# GS_IIM_RFINAL_R_4.net
KiCad netlist of a schematic drawn in EAGLE
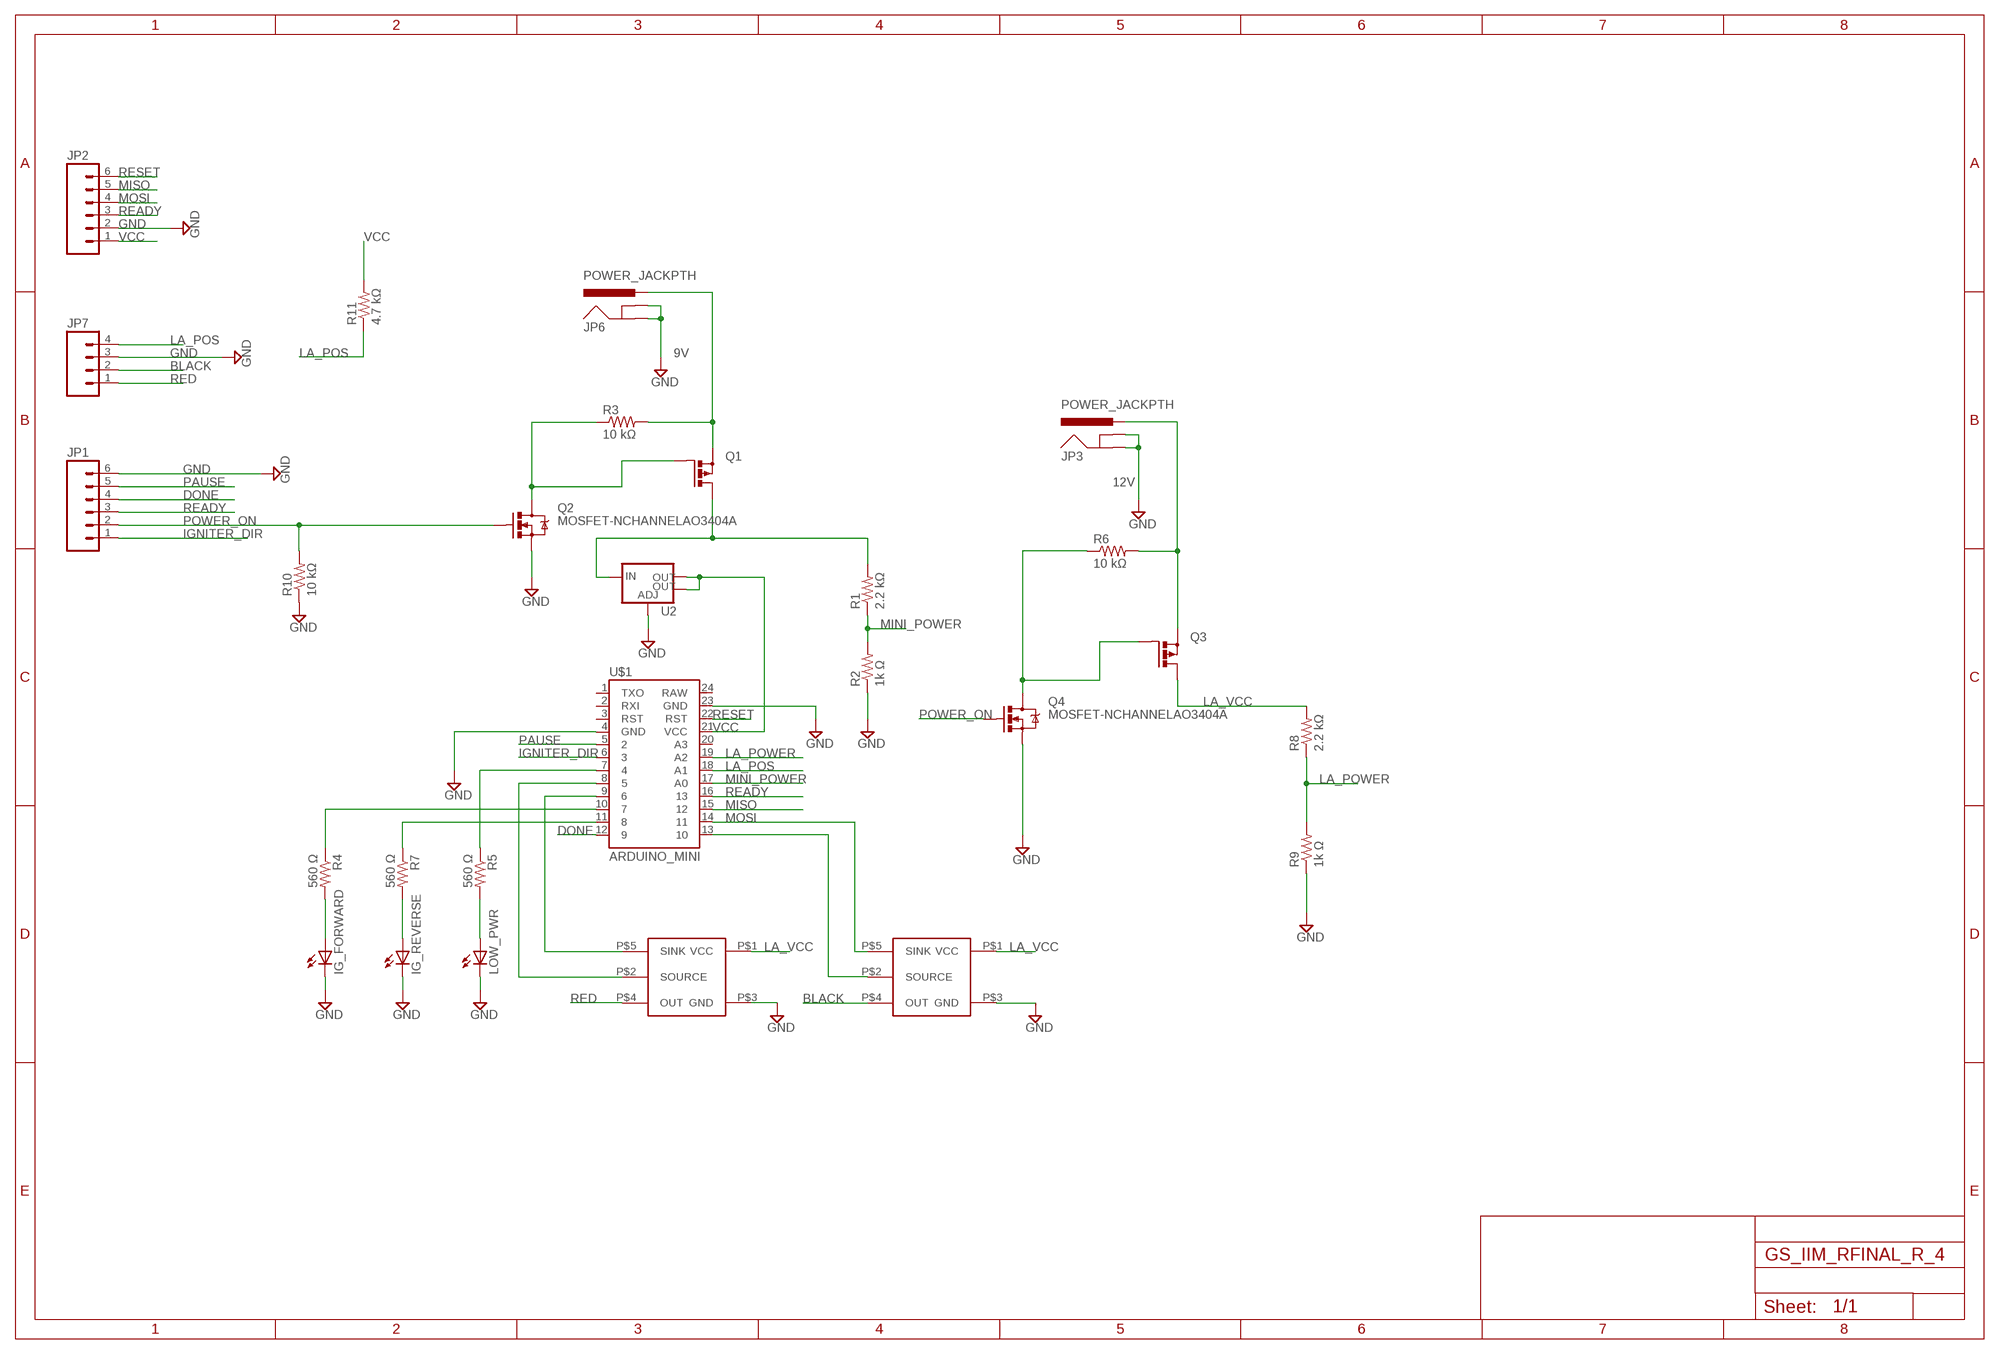
[diagram p0: schematic, sheet 1]

(export (version "E")
  (design (tool "Eeschema 10.0.6"))
  (components
    (comp (ref "IG_FORWARD")
      (value "LED5MM")
      (footprint "eagle-import:LED5MM")
      (libsource (lib "eagle-import") (part "LED5MM"))
    )
    (comp (ref "IG_REVERSE")
      (value "LED5MM")
      (footprint "eagle-import:LED5MM")
      (libsource (lib "eagle-import") (part "LED5MM"))
    )
    (comp (ref "JP1")
      (value "M06SILK_FEMALE_PTH")
      (footprint "eagle-import:1X06")
      (libsource (lib "eagle-import") (part "M06SILK_FEMALE_PTH"))
    )
    (comp (ref "JP2")
      (value "M06SILK_FEMALE_PTH")
      (footprint "eagle-import:1X06")
      (libsource (lib "eagle-import") (part "M06SILK_FEMALE_PTH"))
    )
    (comp (ref "JP3")
      (value "POWER_JACKPTH")
      (footprint "eagle-import:POWER_JACK_PTH")
      (libsource (lib "eagle-import") (part "POWER_JACKPTH"))
    )
    (comp (ref "JP6")
      (value "POWER_JACKPTH")
      (footprint "eagle-import:POWER_JACK_PTH")
      (libsource (lib "eagle-import") (part "POWER_JACKPTH"))
    )
    (comp (ref "JP7")
      (value "M04PTH")
      (footprint "eagle-import:1X04")
      (libsource (lib "eagle-import") (part "M04PTH"))
    )
    (comp (ref "LOW_PWR")
      (value "LED5MM")
      (footprint "eagle-import:LED5MM")
      (libsource (lib "eagle-import") (part "LED5MM"))
    )
    (comp (ref "Q1")
      (value "P-MOSFET-SO8")
      (footprint "eagle-import:SO-08")
      (libsource (lib "eagle-import") (part "P-MOSFET-SO8"))
    )
    (comp (ref "Q2")
      (value "MOSFET-NCHANNELAO3404A")
      (footprint "eagle-import:SOT23-3")
      (libsource (lib "eagle-import") (part "MOSFET-NCHANNELAO3404A"))
    )
    (comp (ref "Q3")
      (value "P-MOSFET-SO8")
      (footprint "eagle-import:SO-08")
      (libsource (lib "eagle-import") (part "P-MOSFET-SO8"))
    )
    (comp (ref "Q4")
      (value "MOSFET-NCHANNELAO3404A")
      (footprint "eagle-import:SOT23-3")
      (libsource (lib "eagle-import") (part "MOSFET-NCHANNELAO3404A"))
    )
    (comp (ref "R1")
      (value "2.2 kΩ")
      (footprint "eagle-import:1206")
      (libsource (lib "eagle-import") (part "RESISTOR1206"))
    )
    (comp (ref "R2")
      (value "1k Ω")
      (footprint "eagle-import:1206")
      (libsource (lib "eagle-import") (part "RESISTOR1206"))
    )
    (comp (ref "R3")
      (value "10 kΩ")
      (footprint "eagle-import:1206")
      (libsource (lib "eagle-import") (part "RESISTOR1206"))
    )
    (comp (ref "R4")
      (value "560 Ω")
      (footprint "eagle-import:1206")
      (libsource (lib "eagle-import") (part "RESISTOR1206"))
    )
    (comp (ref "R5")
      (value "560 Ω")
      (footprint "eagle-import:1206")
      (libsource (lib "eagle-import") (part "RESISTOR1206"))
    )
    (comp (ref "R6")
      (value "10 kΩ")
      (footprint "eagle-import:1206")
      (libsource (lib "eagle-import") (part "RESISTOR1206"))
    )
    (comp (ref "R7")
      (value "560 Ω")
      (footprint "eagle-import:1206")
      (libsource (lib "eagle-import") (part "RESISTOR1206"))
    )
    (comp (ref "R8")
      (value "2.2 kΩ")
      (footprint "eagle-import:1206")
      (libsource (lib "eagle-import") (part "RESISTOR1206"))
    )
    (comp (ref "R9")
      (value "1k Ω")
      (footprint "eagle-import:1206")
      (libsource (lib "eagle-import") (part "RESISTOR1206"))
    )
    (comp (ref "R10")
      (value "10 kΩ")
      (footprint "eagle-import:1206")
      (libsource (lib "eagle-import") (part "RESISTOR1206"))
    )
    (comp (ref "R11")
      (value "4.7 kΩ")
      (footprint "eagle-import:1206")
      (libsource (lib "eagle-import") (part "RESISTOR1206"))
    )
    (comp (ref "U$1")
      (value "ARDUINO_MINI")
      (footprint "eagle-import:ARDUINO_MINI")
      (libsource (lib "eagle-import") (part "ARDUINO_MINI"))
    )
    (comp (ref "U$3")
      (value "UC2950")
      (footprint "eagle-import:TO-220")
      (libsource (lib "eagle-import") (part "UC2950"))
    )
    (comp (ref "U2")
      (value "V_REG_LM1117SOT223")
      (footprint "eagle-import:SOT223")
      (libsource (lib "eagle-import") (part "V_REG_LM1117SOT223"))
    )
    (comp (ref "UC2950_1")
      (value "UC2950")
      (footprint "eagle-import:TO-220")
      (libsource (lib "eagle-import") (part "UC2950"))
    )
  )
  (nets
    (net (code "1") (name "/9V") (class "Default")
      (node (ref "JP6") (pin "PWR") (pinfunction "PWR_PWR") (pintype "bidirectional"))
      (node (ref "Q1") (pin "1") (pinfunction "S_1") (pintype "passive"))
      (node (ref "Q1") (pin "2") (pinfunction "S_2") (pintype "passive"))
      (node (ref "Q1") (pin "3") (pinfunction "S_3") (pintype "passive"))
      (node (ref "R3") (pin "2") (pinfunction "2_2") (pintype "passive"))
    )
    (net (code "2") (name "/12V") (class "Default")
      (node (ref "JP3") (pin "PWR") (pinfunction "PWR_PWR") (pintype "bidirectional"))
      (node (ref "Q3") (pin "1") (pinfunction "S_1") (pintype "passive"))
      (node (ref "Q3") (pin "2") (pinfunction "S_2") (pintype "passive"))
      (node (ref "Q3") (pin "3") (pinfunction "S_3") (pintype "passive"))
      (node (ref "R6") (pin "2") (pinfunction "2_2") (pintype "passive"))
    )
    (net (code "3") (name "/BLACK") (class "Default")
      (node (ref "JP7") (pin "2") (pinfunction "2_2") (pintype "passive"))
      (node (ref "U$3") (pin "P$4") (pinfunction "OUT_P$4") (pintype "bidirectional"))
    )
    (net (code "4") (name "/DONE") (class "Default")
      (node (ref "JP1") (pin "4") (pinfunction "4_4") (pintype "passive"))
      (node (ref "U$1") (pin "12") (pinfunction "9_12") (pintype "bidirectional"))
    )
    (net (code "5") (name "/IGNITER_DIR") (class "Default")
      (node (ref "JP1") (pin "1") (pinfunction "1_1") (pintype "passive"))
      (node (ref "U$1") (pin "6") (pinfunction "3_6") (pintype "bidirectional"))
    )
    (net (code "6") (name "/LA_POS") (class "Default")
      (node (ref "JP7") (pin "4") (pinfunction "4_4") (pintype "passive"))
      (node (ref "R11") (pin "1") (pinfunction "1_1") (pintype "passive"))
      (node (ref "U$1") (pin "18") (pinfunction "A1_18") (pintype "bidirectional"))
    )
    (net (code "7") (name "/LA_POWER") (class "Default")
      (node (ref "R8") (pin "1") (pinfunction "1_1") (pintype "passive"))
      (node (ref "R9") (pin "2") (pinfunction "2_2") (pintype "passive"))
      (node (ref "U$1") (pin "19") (pinfunction "A2_19") (pintype "bidirectional"))
    )
    (net (code "8") (name "/LA_VCC") (class "Default")
      (node (ref "Q3") (pin "5") (pinfunction "D_5") (pintype "passive"))
      (node (ref "Q3") (pin "6") (pinfunction "D_6") (pintype "passive"))
      (node (ref "Q3") (pin "7") (pinfunction "D_7") (pintype "passive"))
      (node (ref "Q3") (pin "8") (pinfunction "D_8") (pintype "passive"))
      (node (ref "R8") (pin "2") (pinfunction "2_2") (pintype "passive"))
      (node (ref "U$3") (pin "P$1") (pinfunction "VCC_P$1") (pintype "bidirectional"))
      (node (ref "UC2950_1") (pin "P$1") (pinfunction "VCC_P$1") (pintype "bidirectional"))
    )
    (net (code "9") (name "/MINI_POWER") (class "Default")
      (node (ref "R1") (pin "1") (pinfunction "1_1") (pintype "passive"))
      (node (ref "R2") (pin "2") (pinfunction "2_2") (pintype "passive"))
      (node (ref "U$1") (pin "17") (pinfunction "A0_17") (pintype "bidirectional"))
    )
    (net (code "10") (name "/MISO") (class "Default")
      (node (ref "JP2") (pin "5") (pinfunction "5_5") (pintype "passive"))
      (node (ref "U$1") (pin "15") (pinfunction "12_15") (pintype "bidirectional"))
    )
    (net (code "11") (name "/MOSI") (class "Default")
      (node (ref "JP2") (pin "4") (pinfunction "4_4") (pintype "passive"))
      (node (ref "U$1") (pin "14") (pinfunction "11_14") (pintype "bidirectional"))
      (node (ref "U$3") (pin "P$5") (pinfunction "SINK_P$5") (pintype "bidirectional"))
    )
    (net (code "12") (name "/PAUSE") (class "Default")
      (node (ref "JP1") (pin "5") (pinfunction "5_5") (pintype "passive"))
      (node (ref "U$1") (pin "5") (pinfunction "2_5") (pintype "bidirectional"))
    )
    (net (code "13") (name "/POWER_ON") (class "Default")
      (node (ref "JP1") (pin "2") (pinfunction "2_2") (pintype "passive"))
      (node (ref "Q2") (pin "1") (pinfunction "G_1") (pintype "passive"))
      (node (ref "Q4") (pin "1") (pinfunction "G_1") (pintype "passive"))
      (node (ref "R10") (pin "2") (pinfunction "2_2") (pintype "passive"))
    )
    (net (code "14") (name "/READY") (class "Default")
      (node (ref "JP1") (pin "3") (pinfunction "3_3") (pintype "passive"))
      (node (ref "JP2") (pin "3") (pinfunction "3_3") (pintype "passive"))
      (node (ref "U$1") (pin "16") (pinfunction "13_16") (pintype "bidirectional"))
    )
    (net (code "15") (name "/RED") (class "Default")
      (node (ref "JP7") (pin "1") (pinfunction "1_1") (pintype "passive"))
      (node (ref "UC2950_1") (pin "P$4") (pinfunction "OUT_P$4") (pintype "bidirectional"))
    )
    (net (code "16") (name "/RESET") (class "Default")
      (node (ref "JP2") (pin "6") (pinfunction "6_6") (pintype "passive"))
      (node (ref "U$1") (pin "22") (pinfunction "RST_22") (pintype "bidirectional"))
    )
    (net (code "17") (name "/VCC") (class "Default")
      (node (ref "JP2") (pin "1") (pinfunction "1_1") (pintype "passive"))
      (node (ref "R11") (pin "2") (pinfunction "2_2") (pintype "passive"))
      (node (ref "U$1") (pin "21") (pinfunction "VCC_21") (pintype "bidirectional"))
      (node (ref "U2") (pin "2") (pinfunction "OUT_2") (pintype "output"))
      (node (ref "U2") (pin "4") (pinfunction "OUT_4") (pintype "output"))
    )
    (net (code "18") (name "GND") (class "Default")
      (node (ref "IG_FORWARD") (pin "K") (pinfunction "C_K") (pintype "passive"))
      (node (ref "IG_REVERSE") (pin "K") (pinfunction "C_K") (pintype "passive"))
      (node (ref "JP1") (pin "6") (pinfunction "6_6") (pintype "passive"))
      (node (ref "JP2") (pin "2") (pinfunction "2_2") (pintype "passive"))
      (node (ref "JP3") (pin "GND") (pinfunction "GND_GND") (pintype "bidirectional"))
      (node (ref "JP3") (pin "GNDBREAK") (pinfunction "GNDBREAK_GNDBREAK") (pintype "bidirectional"))
      (node (ref "JP6") (pin "GND") (pinfunction "GND_GND") (pintype "bidirectional"))
      (node (ref "JP6") (pin "GNDBREAK") (pinfunction "GNDBREAK_GNDBREAK") (pintype "bidirectional"))
      (node (ref "JP7") (pin "3") (pinfunction "3_3") (pintype "passive"))
      (node (ref "LOW_PWR") (pin "K") (pinfunction "C_K") (pintype "passive"))
      (node (ref "Q2") (pin "2") (pinfunction "S_2") (pintype "passive"))
      (node (ref "Q4") (pin "2") (pinfunction "S_2") (pintype "passive"))
      (node (ref "R10") (pin "1") (pinfunction "1_1") (pintype "passive"))
      (node (ref "R2") (pin "1") (pinfunction "1_1") (pintype "passive"))
      (node (ref "R9") (pin "1") (pinfunction "1_1") (pintype "passive"))
      (node (ref "U$1") (pin "23") (pinfunction "GND_23") (pintype "bidirectional"))
      (node (ref "U$1") (pin "4") (pinfunction "GND_4") (pintype "bidirectional"))
      (node (ref "U$3") (pin "P$3") (pinfunction "GND_P$3") (pintype "bidirectional"))
      (node (ref "U2") (pin "1") (pinfunction "ADJ_1") (pintype "input"))
      (node (ref "UC2950_1") (pin "P$3") (pinfunction "GND_P$3") (pintype "bidirectional"))
    )
    (net (code "19") (name "Net-(IG_FORWARD-PadA)") (class "Default")
      (node (ref "IG_FORWARD") (pin "A") (pinfunction "A_A") (pintype "passive"))
      (node (ref "R4") (pin "2") (pinfunction "2_2") (pintype "passive"))
    )
    (net (code "20") (name "Net-(IG_REVERSE-PadA)") (class "Default")
      (node (ref "IG_REVERSE") (pin "A") (pinfunction "A_A") (pintype "passive"))
      (node (ref "R7") (pin "2") (pinfunction "2_2") (pintype "passive"))
    )
    (net (code "21") (name "Net-(LOW_PWR-PadA)") (class "Default")
      (node (ref "LOW_PWR") (pin "A") (pinfunction "A_A") (pintype "passive"))
      (node (ref "R5") (pin "2") (pinfunction "2_2") (pintype "passive"))
    )
    (net (code "22") (name "Net-(Q1-G)") (class "Default")
      (node (ref "Q1") (pin "4") (pinfunction "G_4") (pintype "passive"))
      (node (ref "Q2") (pin "3") (pinfunction "D_3") (pintype "passive"))
      (node (ref "R3") (pin "1") (pinfunction "1_1") (pintype "passive"))
    )
    (net (code "23") (name "Net-(Q3-G)") (class "Default")
      (node (ref "Q3") (pin "4") (pinfunction "G_4") (pintype "passive"))
      (node (ref "Q4") (pin "3") (pinfunction "D_3") (pintype "passive"))
      (node (ref "R6") (pin "1") (pinfunction "1_1") (pintype "passive"))
    )
    (net (code "24") (name "Net-(U$1-4)") (class "Default")
      (node (ref "R5") (pin "1") (pinfunction "1_1") (pintype "passive"))
      (node (ref "U$1") (pin "7") (pinfunction "4_7") (pintype "bidirectional"))
    )
    (net (code "25") (name "Net-(U$1-5)") (class "Default")
      (node (ref "U$1") (pin "8") (pinfunction "5_8") (pintype "bidirectional"))
      (node (ref "UC2950_1") (pin "P$2") (pinfunction "SOURCE_P$2") (pintype "bidirectional"))
    )
    (net (code "26") (name "Net-(U$1-6)") (class "Default")
      (node (ref "U$1") (pin "9") (pinfunction "6_9") (pintype "bidirectional"))
      (node (ref "UC2950_1") (pin "P$5") (pinfunction "SINK_P$5") (pintype "bidirectional"))
    )
    (net (code "27") (name "Net-(U$1-7)") (class "Default")
      (node (ref "R4") (pin "1") (pinfunction "1_1") (pintype "passive"))
      (node (ref "U$1") (pin "10") (pinfunction "7_10") (pintype "bidirectional"))
    )
    (net (code "28") (name "Net-(U$1-8)") (class "Default")
      (node (ref "R7") (pin "1") (pinfunction "1_1") (pintype "passive"))
      (node (ref "U$1") (pin "11") (pinfunction "8_11") (pintype "bidirectional"))
    )
    (net (code "29") (name "Net-(U$1-10)") (class "Default")
      (node (ref "U$1") (pin "13") (pinfunction "10_13") (pintype "bidirectional"))
      (node (ref "U$3") (pin "P$2") (pinfunction "SOURCE_P$2") (pintype "bidirectional"))
    )
    (net (code "30") (name "Net-(U2-IN)") (class "Default")
      (node (ref "Q1") (pin "5") (pinfunction "D_5") (pintype "passive"))
      (node (ref "Q1") (pin "6") (pinfunction "D_6") (pintype "passive"))
      (node (ref "Q1") (pin "7") (pinfunction "D_7") (pintype "passive"))
      (node (ref "Q1") (pin "8") (pinfunction "D_8") (pintype "passive"))
      (node (ref "R1") (pin "2") (pinfunction "2_2") (pintype "passive"))
      (node (ref "U2") (pin "3") (pinfunction "IN_3") (pintype "input"))
    )
    (net (code "31") (name "unconnected-(U$1-A3-Pad20)") (class "Default")
      (node (ref "U$1") (pin "20") (pinfunction "A3_20") (pintype "bidirectional"))
    )
    (net (code "32") (name "unconnected-(U$1-RAW-Pad24)") (class "Default")
      (node (ref "U$1") (pin "24") (pinfunction "RAW_24") (pintype "bidirectional"))
    )
    (net (code "33") (name "unconnected-(U$1-RST-Pad3)") (class "Default")
      (node (ref "U$1") (pin "3") (pinfunction "RST_3") (pintype "bidirectional"))
    )
    (net (code "34") (name "unconnected-(U$1-RXI-Pad2)") (class "Default")
      (node (ref "U$1") (pin "2") (pinfunction "RXI_2") (pintype "bidirectional"))
    )
    (net (code "35") (name "unconnected-(U$1-TXO-Pad1)") (class "Default")
      (node (ref "U$1") (pin "1") (pinfunction "TXO_1") (pintype "bidirectional"))
    )
  )
)
